# ledflikerlessCct.net
KiCad netlist of a schematic drawn in EAGLE
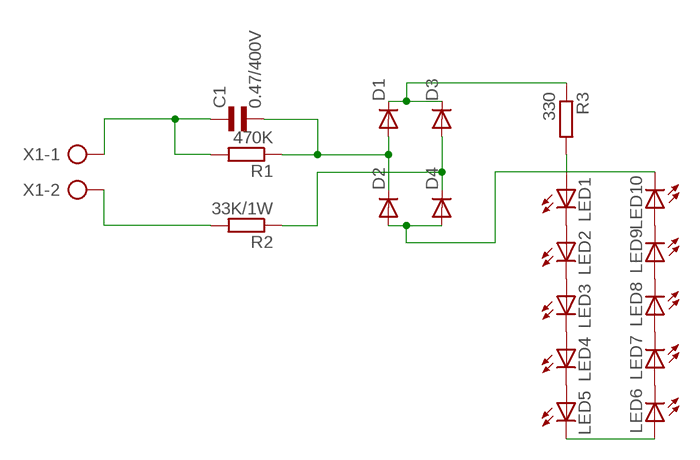
[diagram p0: schematic, sheet 1]

(export (version "E")
  (design (tool "Eeschema 10.0.6"))
  (components
    (comp (ref "C1")
      (value "0.47/400V")
      (footprint "eagle-import:EU25-10")
      (libsource (lib "eagle-import") (part "EL-BI25-10AXIAL"))
    )
    (comp (ref "D1")
      (value "DIODE-D-5")
      (footprint "eagle-import:D-5")
      (libsource (lib "eagle-import") (part "DIODE-D-5"))
    )
    (comp (ref "D2")
      (value "DIODE-D-5")
      (footprint "eagle-import:D-5")
      (libsource (lib "eagle-import") (part "DIODE-D-5"))
    )
    (comp (ref "D3")
      (value "DIODE-D-5")
      (footprint "eagle-import:D-5")
      (libsource (lib "eagle-import") (part "DIODE-D-5"))
    )
    (comp (ref "D4")
      (value "DIODE-D-5")
      (footprint "eagle-import:D-5")
      (libsource (lib "eagle-import") (part "DIODE-D-5"))
    )
    (comp (ref "LED1")
      (value "LEDP-LCC-2-BACK")
      (footprint "eagle-import:P-LCC-2-TOPLED-RG")
      (libsource (lib "eagle-import") (part "LEDP-LCC-2-BACK"))
    )
    (comp (ref "LED2")
      (value "LEDP-LCC-2-BACK")
      (footprint "eagle-import:P-LCC-2-TOPLED-RG")
      (libsource (lib "eagle-import") (part "LEDP-LCC-2-BACK"))
    )
    (comp (ref "LED3")
      (value "LEDP-LCC-2-BACK")
      (footprint "eagle-import:P-LCC-2-TOPLED-RG")
      (libsource (lib "eagle-import") (part "LEDP-LCC-2-BACK"))
    )
    (comp (ref "LED4")
      (value "LEDP-LCC-2-BACK")
      (footprint "eagle-import:P-LCC-2-TOPLED-RG")
      (libsource (lib "eagle-import") (part "LEDP-LCC-2-BACK"))
    )
    (comp (ref "LED5")
      (value "LEDP-LCC-2-BACK")
      (footprint "eagle-import:P-LCC-2-TOPLED-RG")
      (libsource (lib "eagle-import") (part "LEDP-LCC-2-BACK"))
    )
    (comp (ref "LED6")
      (value "LEDP-LCC-2-BACK")
      (footprint "eagle-import:P-LCC-2-TOPLED-RG")
      (libsource (lib "eagle-import") (part "LEDP-LCC-2-BACK"))
    )
    (comp (ref "LED7")
      (value "LEDP-LCC-2-BACK")
      (footprint "eagle-import:P-LCC-2-TOPLED-RG")
      (libsource (lib "eagle-import") (part "LEDP-LCC-2-BACK"))
    )
    (comp (ref "LED8")
      (value "LEDP-LCC-2-BACK")
      (footprint "eagle-import:P-LCC-2-TOPLED-RG")
      (libsource (lib "eagle-import") (part "LEDP-LCC-2-BACK"))
    )
    (comp (ref "LED9")
      (value "LEDP-LCC-2-BACK")
      (footprint "eagle-import:P-LCC-2-TOPLED-RG")
      (libsource (lib "eagle-import") (part "LEDP-LCC-2-BACK"))
    )
    (comp (ref "LED10")
      (value "LEDP-LCC-2-BACK")
      (footprint "eagle-import:P-LCC-2-TOPLED-RG")
      (libsource (lib "eagle-import") (part "LEDP-LCC-2-BACK"))
    )
    (comp (ref "R1")
      (value "470K")
      (footprint "eagle-import:0207_10")
      (libsource (lib "eagle-import") (part "R-EU_0207/10"))
    )
    (comp (ref "R2")
      (value "33K/1W")
      (footprint "eagle-import:0411_15")
      (libsource (lib "eagle-import") (part "R-EU_0411/15"))
    )
    (comp (ref "R3")
      (value "330")
      (footprint "eagle-import:R1206")
      (libsource (lib "eagle-import") (part "R-EU_R1206"))
    )
    (comp (ref "X1")
      (value "AK300/2")
      (footprint "eagle-import:AK300_2")
      (libsource (lib "eagle-import") (part "AK300/2"))
    )
  )
  (nets
    (net (code "1") (name "Net-(C1-Pad2)") (class "Default")
      (node (ref "C1") (pin "2") (pinfunction "2_2") (pintype "passive"))
      (node (ref "D1") (pin "A") (pinfunction "A_A") (pintype "passive"))
      (node (ref "D2") (pin "C") (pinfunction "C_C") (pintype "passive"))
      (node (ref "R1") (pin "1") (pinfunction "1_1") (pintype "passive"))
    )
    (net (code "2") (name "Net-(D1-PadC)") (class "Default")
      (node (ref "D1") (pin "C") (pinfunction "C_C") (pintype "passive"))
      (node (ref "D3") (pin "C") (pinfunction "C_C") (pintype "passive"))
      (node (ref "R3") (pin "1") (pinfunction "1_1") (pintype "passive"))
    )
    (net (code "3") (name "Net-(D2-PadA)") (class "Default")
      (node (ref "D2") (pin "A") (pinfunction "A_A") (pintype "passive"))
      (node (ref "D4") (pin "A") (pinfunction "A_A") (pintype "passive"))
      (node (ref "LED10") (pin "C") (pinfunction "C_C") (pintype "passive"))
    )
    (net (code "4") (name "Net-(D3-PadA)") (class "Default")
      (node (ref "D3") (pin "A") (pinfunction "A_A") (pintype "passive"))
      (node (ref "D4") (pin "C") (pinfunction "C_C") (pintype "passive"))
      (node (ref "R2") (pin "1") (pinfunction "1_1") (pintype "passive"))
    )
    (net (code "5") (name "Net-(LED1-PadA)") (class "Default")
      (node (ref "LED1") (pin "A") (pinfunction "A_A") (pintype "passive"))
      (node (ref "R3") (pin "2") (pinfunction "2_2") (pintype "passive"))
    )
    (net (code "6") (name "Net-(LED1-PadC)") (class "Default")
      (node (ref "LED1") (pin "C") (pinfunction "C_C") (pintype "passive"))
      (node (ref "LED2") (pin "A") (pinfunction "A_A") (pintype "passive"))
    )
    (net (code "7") (name "Net-(LED2-PadC)") (class "Default")
      (node (ref "LED2") (pin "C") (pinfunction "C_C") (pintype "passive"))
      (node (ref "LED3") (pin "A") (pinfunction "A_A") (pintype "passive"))
    )
    (net (code "8") (name "Net-(LED3-PadC)") (class "Default")
      (node (ref "LED3") (pin "C") (pinfunction "C_C") (pintype "passive"))
      (node (ref "LED4") (pin "A") (pinfunction "A_A") (pintype "passive"))
    )
    (net (code "9") (name "Net-(LED4-PadC)") (class "Default")
      (node (ref "LED4") (pin "C") (pinfunction "C_C") (pintype "passive"))
      (node (ref "LED5") (pin "A") (pinfunction "A_A") (pintype "passive"))
    )
    (net (code "10") (name "Net-(LED5-PadC)") (class "Default")
      (node (ref "LED5") (pin "C") (pinfunction "C_C") (pintype "passive"))
      (node (ref "LED6") (pin "A") (pinfunction "A_A") (pintype "passive"))
    )
    (net (code "11") (name "Net-(LED6-PadC)") (class "Default")
      (node (ref "LED6") (pin "C") (pinfunction "C_C") (pintype "passive"))
      (node (ref "LED7") (pin "A") (pinfunction "A_A") (pintype "passive"))
    )
    (net (code "12") (name "Net-(LED7-PadC)") (class "Default")
      (node (ref "LED7") (pin "C") (pinfunction "C_C") (pintype "passive"))
      (node (ref "LED8") (pin "A") (pinfunction "A_A") (pintype "passive"))
    )
    (net (code "13") (name "Net-(LED8-PadC)") (class "Default")
      (node (ref "LED8") (pin "C") (pinfunction "C_C") (pintype "passive"))
      (node (ref "LED9") (pin "A") (pinfunction "A_A") (pintype "passive"))
    )
    (net (code "14") (name "Net-(LED10-PadA)") (class "Default")
      (node (ref "LED10") (pin "A") (pinfunction "A_A") (pintype "passive"))
      (node (ref "LED9") (pin "C") (pinfunction "C_C") (pintype "passive"))
    )
    (net (code "15") (name "Net-(X1A-KL)") (class "Default")
      (node (ref "C1") (pin "1") (pinfunction "1_1") (pintype "passive"))
      (node (ref "R1") (pin "2") (pinfunction "2_2") (pintype "passive"))
      (node (ref "X1") (pin "1") (pinfunction "KL_1") (pintype "passive"))
    )
    (net (code "16") (name "Net-(X1B-KL)") (class "Default")
      (node (ref "R2") (pin "2") (pinfunction "2_2") (pintype "passive"))
      (node (ref "X1") (pin "2") (pinfunction "KL_2") (pintype "passive"))
    )
  )
)
